# Precharge.net
KiCad netlist of a schematic drawn in Altium Designer
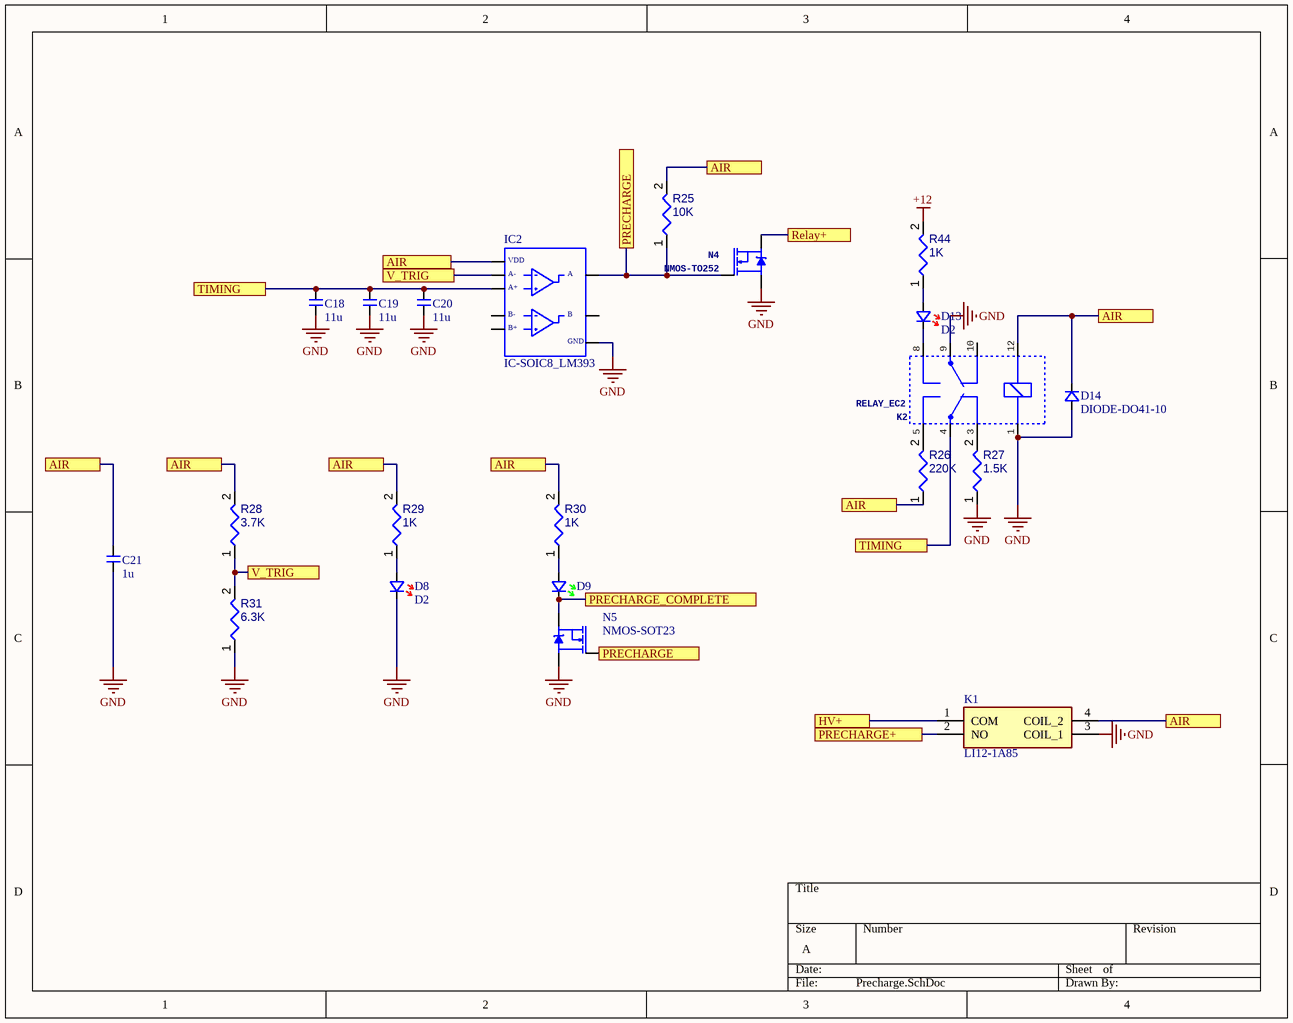
[diagram p0: Precharge.SchDoc]

(export (version "E")
  (design (tool "Eeschema 10.0.6"))
  (components
    (comp (ref "C18")
      (value "11u")
      (footprint "CAP-0603")
      (fields (field (name "SOURCE") "ife19_Elec_Library.SchLib"))
      (libsource (lib "Illini Formula Electric") (part "CAP-0603"))
    )
    (comp (ref "C19")
      (value "11u")
      (footprint "CAP-0603")
      (fields (field (name "SOURCE") "ife19_Elec_Library.SchLib"))
      (libsource (lib "Illini Formula Electric") (part "CAP-0603"))
    )
    (comp (ref "C20")
      (value "11u")
      (footprint "CAP-0603")
      (fields (field (name "SOURCE") "ife19_Elec_Library.SchLib"))
      (libsource (lib "Illini Formula Electric") (part "CAP-0603"))
    )
    (comp (ref "C21")
      (value "1u")
      (footprint "CAP-0603")
      (fields (field (name "SOURCE") "ife19_Elec_Library.SchLib"))
      (libsource (lib "Illini Formula Electric") (part "CAP-0603"))
    )
    (comp (ref "D8")
      (value "D2")
      (footprint "LEDRED-0603")
      (fields (field (name "SOURCE") "ife19_Elec_Library.SchLib"))
      (libsource (lib "Illini Formula Electric") (part "LED_XZFBB45S"))
    )
    (comp (ref "D9")
      (value "LEDGREEN-1806-RIGHT")
      (footprint "LEDGREEN-1806-RIGHT")
      (fields (field (name "SOURCE") "ife19_Elec_Library.SchLib"))
      (libsource (lib "Illini Formula Electric") (part "LEDGREEN-1806-RIGHT"))
    )
    (comp (ref "D13")
      (value "D2")
      (footprint "LEDRED-0603")
      (fields (field (name "SOURCE") "ife19_Elec_Library.SchLib"))
      (libsource (lib "Illini Formula Electric") (part "LED_XZFBB45S"))
    )
    (comp (ref "D14")
      (value "DIODE-DO41-10")
      (footprint "DO41-10")
      (fields (field (name "SOURCE") "ife19_Elec_Library.SchLib"))
      (libsource (lib "Illini Formula Electric") (part "DIODE-DO41-10"))
    )
    (comp (ref "IC2")
      (value "IC-SOIC8_LM393")
      (footprint "SOIC8")
      (fields (field (name "SOURCE") "ife19_Elec_Library.SchLib"))
      (libsource (lib "Illini Formula Electric") (part "IC-SOIC8_LM393"))
    )
    (comp (ref "K1")
      (value "LI12-1A85")
      (footprint "SamacSys:LI121A85")
      (description "Relay or Contactor")
      (fields (field (name "MOUSER PART NUMBER") "876-LI12-1A85"))
      (libsource (lib "*") (part "LI12-1A85"))
    )
    (comp (ref "K2")
      (value "RELAY_EC2")
      (footprint "RELAY-DPDT_EC2")
      (fields (field (name "SOURCE") "ife19_Elec_Library.SchLib"))
      (libsource (lib "Illini Formula Electric") (part "RELAY_EC2"))
    )
    (comp (ref "N4")
      (value "NMOS-TO252")
      (footprint "TO252")
      (fields
        (field (name "SOURCE") "ife19_Elec_Library.SchLib")
        (field (name "LIBRARYNAME") "IFE_Transistors")
      )
      (libsource (lib "Illini Formula Electric") (part "NMOS-TO252"))
    )
    (comp (ref "N5")
      (value "NMOS-SOT23")
      (footprint "SOT23")
      (fields (field (name "SOURCE") "ife19_Elec_Library.SchLib"))
      (libsource (lib "Illini Formula Electric") (part "NMOS-SOT23"))
    )
    (comp (ref "R25")
      (value "10K")
      (footprint "RESC0805(2012)_L")
      (description "Chip Resistor, 43,2 kOhms, +/-1 %, 63 mW, -55 to 155 degC, 0402")
      (fields (field (name "AVAILABLE PREVIEW IMAGES") "2D"))
      (libsource (lib "Illini Formula Electric") (part "Symbol"))
    )
    (comp (ref "R26")
      (value "220K")
      (footprint "RESC0805(2012)_L")
      (description "Chip Resistor, 43,2 kOhms, +/-1 %, 63 mW, -55 to 155 degC, 0402")
      (fields (field (name "AVAILABLE PREVIEW IMAGES") "2D"))
      (libsource (lib "Illini Formula Electric") (part "Symbol"))
    )
    (comp (ref "R27")
      (value "1.5K")
      (footprint "RESC0805(2012)_L")
      (description "Chip Resistor, 43,2 kOhms, +/-1 %, 63 mW, -55 to 155 degC, 0402")
      (fields (field (name "AVAILABLE PREVIEW IMAGES") "2D"))
      (libsource (lib "Illini Formula Electric") (part "Symbol"))
    )
    (comp (ref "R28")
      (value "3.7K")
      (footprint "RESC0805(2012)_L")
      (description "Chip Resistor, 43,2 kOhms, +/-1 %, 63 mW, -55 to 155 degC, 0402")
      (fields (field (name "AVAILABLE PREVIEW IMAGES") "2D"))
      (libsource (lib "Illini Formula Electric") (part "Symbol"))
    )
    (comp (ref "R29")
      (value "1K")
      (footprint "RESC0805(2012)_L")
      (description "Chip Resistor, 43,2 kOhms, +/-1 %, 63 mW, -55 to 155 degC, 0402")
      (fields (field (name "AVAILABLE PREVIEW IMAGES") "2D"))
      (libsource (lib "Illini Formula Electric") (part "Symbol"))
    )
    (comp (ref "R30")
      (value "1K")
      (footprint "RESC0805(2012)_L")
      (description "Chip Resistor, 43,2 kOhms, +/-1 %, 63 mW, -55 to 155 degC, 0402")
      (fields (field (name "AVAILABLE PREVIEW IMAGES") "2D"))
      (libsource (lib "Illini Formula Electric") (part "Symbol"))
    )
    (comp (ref "R31")
      (value "6.3K")
      (footprint "RESC0805(2012)_L")
      (description "Chip Resistor, 43,2 kOhms, +/-1 %, 63 mW, -55 to 155 degC, 0402")
      (fields (field (name "AVAILABLE PREVIEW IMAGES") "2D"))
      (libsource (lib "Illini Formula Electric") (part "Symbol"))
    )
    (comp (ref "R44")
      (value "1K")
      (footprint "RESC0805(2012)_L")
      (description "Chip Resistor, 43,2 kOhms, +/-1 %, 63 mW, -55 to 155 degC, 0402")
      (fields (field (name "AVAILABLE PREVIEW IMAGES") "2D"))
      (libsource (lib "Illini Formula Electric") (part "Symbol"))
    )
  )
  (nets
    (net (code "1") (name "+12") (class "Default")
      (node (ref "R44") (pin "2") (pinfunction "2_2") (pintype "passive"))
    )
    (net (code "2") (name "/AIR") (class "Default")
      (node (ref "C21") (pin "1") (pinfunction "1_1") (pintype "passive"))
      (node (ref "D14") (pin "K") (pinfunction "K_K") (pintype "passive"))
      (node (ref "IC2") (pin "8") (pinfunction "8_8") (pintype "passive"))
      (node (ref "K1") (pin "4") (pinfunction "COIL_2_4") (pintype "passive"))
      (node (ref "K2") (pin "12") (pintype "passive"))
      (node (ref "R25") (pin "2") (pinfunction "2_2") (pintype "passive"))
      (node (ref "R26") (pin "1") (pinfunction "1_1") (pintype "passive"))
      (node (ref "R28") (pin "2") (pinfunction "2_2") (pintype "passive"))
      (node (ref "R29") (pin "2") (pinfunction "2_2") (pintype "passive"))
      (node (ref "R30") (pin "2") (pinfunction "2_2") (pintype "passive"))
    )
    (net (code "3") (name "/HV+") (class "Default")
      (node (ref "K1") (pin "1") (pinfunction "COM_1") (pintype "passive"))
    )
    (net (code "4") (name "/PRECHARGE") (class "Default")
      (node (ref "IC2") (pin "1") (pinfunction "1_1") (pintype "passive"))
      (node (ref "N4") (pin "1") (pinfunction "G_1") (pintype "passive"))
      (node (ref "N5") (pin "1") (pinfunction "G_1") (pintype "passive"))
      (node (ref "R25") (pin "1") (pinfunction "1_1") (pintype "passive"))
    )
    (net (code "5") (name "/PRECHARGE+") (class "Default")
      (node (ref "K1") (pin "2") (pinfunction "NO_2") (pintype "passive"))
    )
    (net (code "6") (name "/PRECHARGE_COMPLETE") (class "Default")
      (node (ref "D9") (pin "K") (pinfunction "K_K") (pintype "passive"))
      (node (ref "N5") (pin "3") (pinfunction "D_3") (pintype "passive"))
    )
    (net (code "7") (name "/Relay+") (class "Default")
      (node (ref "N4") (pin "3") (pinfunction "D_3") (pintype "passive"))
    )
    (net (code "8") (name "/TIMING") (class "Default")
      (node (ref "C18") (pin "1") (pinfunction "1_1") (pintype "passive"))
      (node (ref "C19") (pin "1") (pinfunction "1_1") (pintype "passive"))
      (node (ref "C20") (pin "1") (pinfunction "1_1") (pintype "passive"))
      (node (ref "IC2") (pin "3") (pinfunction "3_3") (pintype "passive"))
      (node (ref "K2") (pin "4") (pintype "passive"))
    )
    (net (code "9") (name "/V_TRIG") (class "Default")
      (node (ref "IC2") (pin "2") (pinfunction "2_2") (pintype "passive"))
      (node (ref "R28") (pin "1") (pinfunction "1_1") (pintype "passive"))
      (node (ref "R31") (pin "2") (pinfunction "2_2") (pintype "passive"))
    )
    (net (code "10") (name "GND") (class "Default")
      (node (ref "C18") (pin "2") (pinfunction "2_2") (pintype "passive"))
      (node (ref "C19") (pin "2") (pinfunction "2_2") (pintype "passive"))
      (node (ref "C20") (pin "2") (pinfunction "2_2") (pintype "passive"))
      (node (ref "C21") (pin "2") (pinfunction "2_2") (pintype "passive"))
      (node (ref "D14") (pin "A") (pinfunction "A_A") (pintype "passive"))
      (node (ref "D8") (pin "K") (pinfunction "K_K") (pintype "passive"))
      (node (ref "IC2") (pin "4") (pinfunction "4_4") (pintype "passive"))
      (node (ref "K1") (pin "3") (pinfunction "COIL_1_3") (pintype "passive"))
      (node (ref "K2") (pin "1") (pintype "passive"))
      (node (ref "K2") (pin "9") (pintype "passive"))
      (node (ref "N4") (pin "2") (pinfunction "S_2") (pintype "passive"))
      (node (ref "N5") (pin "2") (pinfunction "S_2") (pintype "passive"))
      (node (ref "R27") (pin "1") (pinfunction "1_1") (pintype "passive"))
      (node (ref "R31") (pin "1") (pinfunction "1_1") (pintype "passive"))
    )
    (net (code "11") (name "Net-(D8-PadA)") (class "Default")
      (node (ref "D8") (pin "A") (pinfunction "A_A") (pintype "passive"))
      (node (ref "R29") (pin "1") (pinfunction "1_1") (pintype "passive"))
    )
    (net (code "12") (name "Net-(D9-PadA)") (class "Default")
      (node (ref "D9") (pin "A") (pinfunction "A_A") (pintype "passive"))
      (node (ref "R30") (pin "1") (pinfunction "1_1") (pintype "passive"))
    )
    (net (code "13") (name "Net-(D13-PadA)") (class "Default")
      (node (ref "D13") (pin "A") (pinfunction "A_A") (pintype "passive"))
      (node (ref "R44") (pin "1") (pinfunction "1_1") (pintype "passive"))
    )
    (net (code "14") (name "Net-(D13-PadK)") (class "Default")
      (node (ref "D13") (pin "K") (pinfunction "K_K") (pintype "passive"))
      (node (ref "K2") (pin "8") (pintype "passive"))
    )
    (net (code "15") (name "Net-(K2-Pad3)") (class "Default")
      (node (ref "K2") (pin "3") (pintype "passive"))
      (node (ref "R27") (pin "2") (pinfunction "2_2") (pintype "passive"))
    )
    (net (code "16") (name "Net-(K2-Pad5)") (class "Default")
      (node (ref "K2") (pin "5") (pintype "passive"))
      (node (ref "R26") (pin "2") (pinfunction "2_2") (pintype "passive"))
    )
    (net (code "17") (name "unconnected-(IC2-Pad5)") (class "Default")
      (node (ref "IC2") (pin "5") (pinfunction "5_5") (pintype "passive"))
    )
    (net (code "18") (name "unconnected-(IC2-Pad6)") (class "Default")
      (node (ref "IC2") (pin "6") (pinfunction "6_6") (pintype "passive"))
    )
    (net (code "19") (name "unconnected-(IC2-Pad7)") (class "Default")
      (node (ref "IC2") (pin "7") (pinfunction "7_7") (pintype "passive"))
    )
    (net (code "20") (name "unconnected-(K2-Pad10)") (class "Default")
      (node (ref "K2") (pin "10") (pintype "passive"))
    )
  )
)
